# resistors_prototype.net
KiCad netlist of a schematic drawn in EAGLE
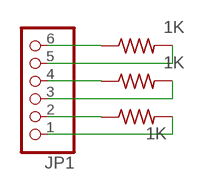
[diagram p0: schematic, sheet 1]

(export (version "E")
  (design (tool "Eeschema 10.0.6"))
  (components
    (comp (ref "JP1")
      (value "PINHD-1X6")
      (footprint "eagle-import:1X06")
      (libsource (lib "eagle-import") (part "PINHD-1X6"))
    )
    (comp (ref "R2")
      (value "1K")
      (footprint "eagle-import:R0805")
      (libsource (lib "eagle-import") (part "R-US_R0805"))
    )
    (comp (ref "R4")
      (value "1K")
      (footprint "eagle-import:R0805")
      (libsource (lib "eagle-import") (part "R-US_R0805"))
    )
    (comp (ref "R5")
      (value "1K")
      (footprint "eagle-import:R0805")
      (libsource (lib "eagle-import") (part "R-US_R0805"))
    )
  )
  (nets
    (net (code "1") (name "Net-(JP1-Pad1)") (class "Default")
      (node (ref "JP1") (pin "1") (pinfunction "1_1") (pintype "passive"))
      (node (ref "R5") (pin "2") (pinfunction "2_2") (pintype "passive"))
    )
    (net (code "2") (name "Net-(JP1-Pad2)") (class "Default")
      (node (ref "JP1") (pin "2") (pinfunction "2_2") (pintype "passive"))
      (node (ref "R5") (pin "1") (pinfunction "1_1") (pintype "passive"))
    )
    (net (code "3") (name "Net-(JP1-Pad3)") (class "Default")
      (node (ref "JP1") (pin "3") (pinfunction "3_3") (pintype "passive"))
      (node (ref "R4") (pin "2") (pinfunction "2_2") (pintype "passive"))
    )
    (net (code "4") (name "Net-(JP1-Pad4)") (class "Default")
      (node (ref "JP1") (pin "4") (pinfunction "4_4") (pintype "passive"))
      (node (ref "R4") (pin "1") (pinfunction "1_1") (pintype "passive"))
    )
    (net (code "5") (name "Net-(JP1-Pad5)") (class "Default")
      (node (ref "JP1") (pin "5") (pinfunction "5_5") (pintype "passive"))
      (node (ref "R2") (pin "2") (pinfunction "2_2") (pintype "passive"))
    )
    (net (code "6") (name "Net-(JP1-Pad6)") (class "Default")
      (node (ref "JP1") (pin "6") (pinfunction "6_6") (pintype "passive"))
      (node (ref "R2") (pin "1") (pinfunction "1_1") (pintype "passive"))
    )
  )
)
